# Transistor_Tester.net
KiCad netlist of a schematic drawn in EAGLE
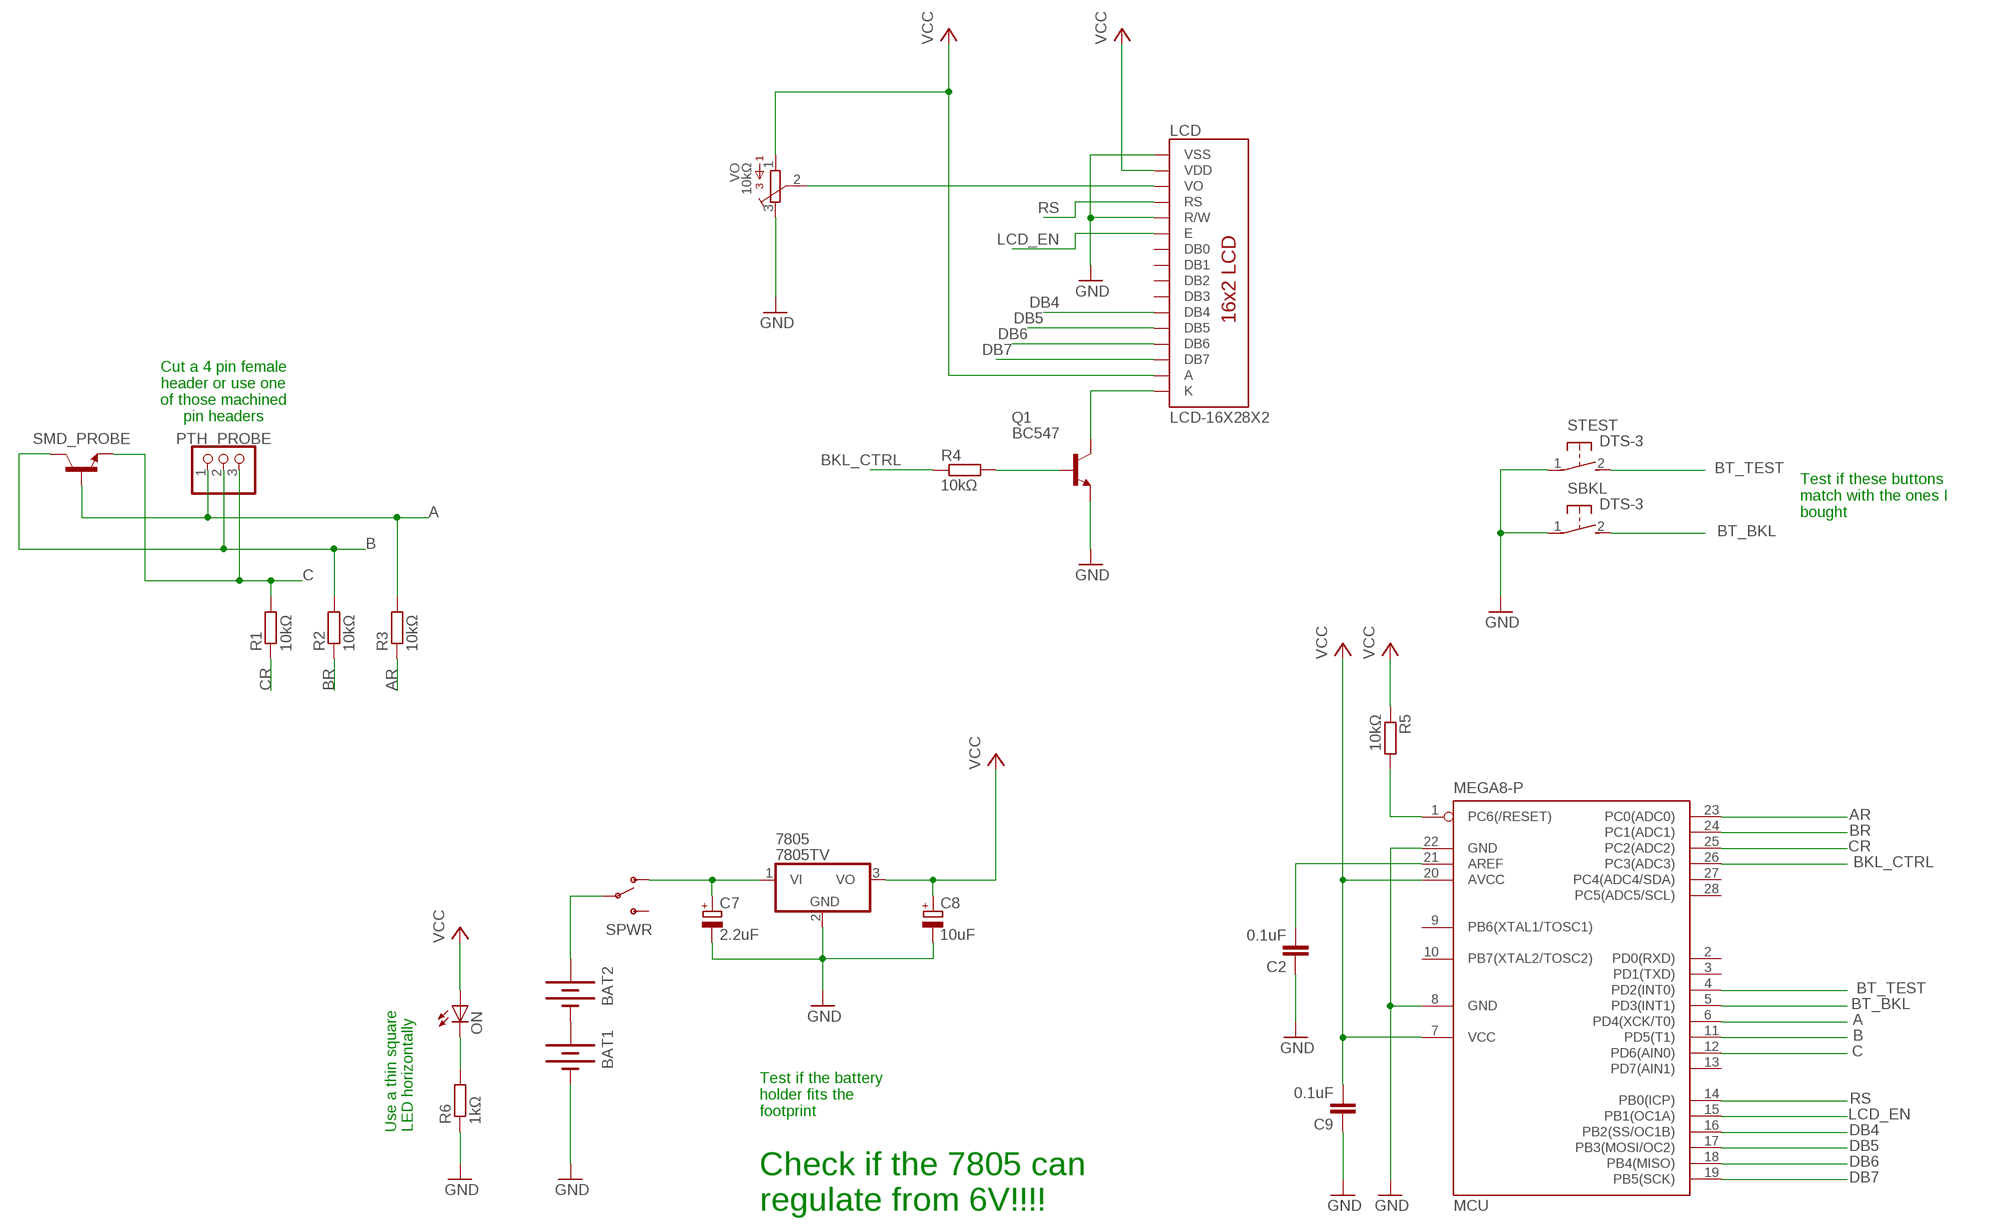
[diagram p0: schematic, sheet 1]

(export (version "E")
  (design (tool "Eeschema 10.0.6"))
  (components
    (comp (ref "7805")
      (value "7805TV")
      (footprint "eagle-import:TO220V")
      (libsource (lib "eagle-import") (part "78TV05"))
    )
    (comp (ref "BAT1")
      (value "20mm coincell")
      (footprint "eagle-import:BATTCON_20MM_4LEGS")
      (libsource (lib "eagle-import") (part "BATTERY20MM_4LEGS"))
    )
    (comp (ref "BAT2")
      (value "20mm coincell")
      (footprint "eagle-import:BATTCON_20MM_4LEGS")
      (libsource (lib "eagle-import") (part "BATTERY20MM_4LEGS"))
    )
    (comp (ref "C2")
      (value "0.1uF")
      (footprint "eagle-import:C025-025X050")
      (libsource (lib "eagle-import") (part "C-EU025-025X050"))
    )
    (comp (ref "C7")
      (value "2.2uF")
      (footprint "eagle-import:E2,5-6")
      (libsource (lib "eagle-import") (part "CPOL-EUE2.5-6"))
    )
    (comp (ref "C8")
      (value "10uF")
      (footprint "eagle-import:E2,5-6")
      (libsource (lib "eagle-import") (part "CPOL-EUE2.5-6"))
    )
    (comp (ref "C9")
      (value "0.1uF")
      (footprint "eagle-import:C050-025X075")
      (libsource (lib "eagle-import") (part "C-EU050-025X075"))
    )
    (comp (ref "LCD")
      (value "LCD-16X28X2")
      (footprint "eagle-import:LCD-8X2")
      (libsource (lib "eagle-import") (part "LCD-16X28X2"))
    )
    (comp (ref "MCU")
      (value "MEGA8-P")
      (footprint "eagle-import:DIL28-3")
      (libsource (lib "eagle-import") (part "MEGA8-P"))
    )
    (comp (ref "ON")
      (value "LED3MM")
      (footprint "eagle-import:LED3MM")
      (libsource (lib "eagle-import") (part "LED3MM"))
    )
    (comp (ref "PTH_PROBE")
      (value "PINHD-1X3")
      (footprint "eagle-import:1X03")
      (libsource (lib "eagle-import") (part "PINHD-1X3"))
    )
    (comp (ref "Q1")
      (value "BC547")
      (footprint "eagle-import:TO92")
      (libsource (lib "eagle-import") (part "BC547"))
    )
    (comp (ref "R1")
      (value "10kΩ")
      (footprint "eagle-import:0207_10")
      (libsource (lib "eagle-import") (part "resistor_R-EU_0207/10"))
    )
    (comp (ref "R2")
      (value "10kΩ")
      (footprint "eagle-import:0207_10")
      (libsource (lib "eagle-import") (part "resistor_R-EU_0207/10"))
    )
    (comp (ref "R3")
      (value "10kΩ")
      (footprint "eagle-import:0207_10")
      (libsource (lib "eagle-import") (part "resistor_R-EU_0207/10"))
    )
    (comp (ref "R4")
      (value "10kΩ")
      (footprint "eagle-import:0207_10")
      (libsource (lib "eagle-import") (part "R-EU_0207/10"))
    )
    (comp (ref "R5")
      (value "10kΩ")
      (footprint "eagle-import:0207_10")
      (libsource (lib "eagle-import") (part "R-EU_0207/10"))
    )
    (comp (ref "R6")
      (value "1kΩ")
      (footprint "eagle-import:0207_10")
      (libsource (lib "eagle-import") (part "R-EU_0207/10"))
    )
    (comp (ref "SBKL")
      (value "DTS-3")
      (footprint "eagle-import:DTS-3")
      (libsource (lib "eagle-import") (part "DTS-3"))
    )
    (comp (ref "SMD_PROBE")
      (value "BC817-25SMD")
      (footprint "eagle-import:SOT23-BEC")
      (libsource (lib "eagle-import") (part "BC817SMD-25"))
    )
    (comp (ref "SPWR")
      (value "SWITCH-SPDTPTH")
      (footprint "eagle-import:SWITCH-SPDT")
      (libsource (lib "eagle-import") (part "SWITCH-SPDTPTH"))
    )
    (comp (ref "STEST")
      (value "DTS-3")
      (footprint "eagle-import:DTS-3")
      (libsource (lib "eagle-import") (part "DTS-3"))
    )
    (comp (ref "VO")
      (value "10kΩ")
      (footprint "eagle-import:3362H")
      (libsource (lib "eagle-import") (part "3362H"))
    )
  )
  (nets
    (net (code "1") (name "/A") (class "Default")
      (node (ref "MCU") (pin "6") (pinfunction "PD4(XCK/T0)_6") (pintype "bidirectional"))
      (node (ref "PTH_PROBE") (pin "1") (pinfunction "1_1") (pintype "passive"))
      (node (ref "R3") (pin "2") (pinfunction "2_2") (pintype "passive"))
      (node (ref "SMD_PROBE") (pin "B") (pinfunction "B_B") (pintype "passive"))
    )
    (net (code "2") (name "/AR") (class "Default")
      (node (ref "MCU") (pin "23") (pinfunction "PC0(ADC0)_23") (pintype "bidirectional"))
      (node (ref "R3") (pin "1") (pinfunction "1_1") (pintype "passive"))
    )
    (net (code "3") (name "/B") (class "Default")
      (node (ref "MCU") (pin "11") (pinfunction "PD5(T1)_11") (pintype "bidirectional"))
      (node (ref "PTH_PROBE") (pin "2") (pinfunction "2_2") (pintype "passive"))
      (node (ref "R2") (pin "2") (pinfunction "2_2") (pintype "passive"))
      (node (ref "SMD_PROBE") (pin "C") (pinfunction "C_C") (pintype "passive"))
    )
    (net (code "4") (name "/BKL_CTRL") (class "Default")
      (node (ref "MCU") (pin "26") (pinfunction "PC3(ADC3)_26") (pintype "bidirectional"))
      (node (ref "R4") (pin "1") (pinfunction "1_1") (pintype "passive"))
    )
    (net (code "5") (name "/BR") (class "Default")
      (node (ref "MCU") (pin "24") (pinfunction "PC1(ADC1)_24") (pintype "bidirectional"))
      (node (ref "R2") (pin "1") (pinfunction "1_1") (pintype "passive"))
    )
    (net (code "6") (name "/BT_BKL") (class "Default")
      (node (ref "MCU") (pin "5") (pinfunction "PD3(INT1)_5") (pintype "bidirectional"))
      (node (ref "SBKL") (pin "2") (pinfunction "2_2") (pintype "passive"))
    )
    (net (code "7") (name "/BT_TEST") (class "Default")
      (node (ref "MCU") (pin "4") (pinfunction "PD2(INT0)_4") (pintype "bidirectional"))
      (node (ref "STEST") (pin "2") (pinfunction "2_2") (pintype "passive"))
    )
    (net (code "8") (name "/C") (class "Default")
      (node (ref "MCU") (pin "12") (pinfunction "PD6(AIN0)_12") (pintype "bidirectional"))
      (node (ref "PTH_PROBE") (pin "3") (pinfunction "3_3") (pintype "passive"))
      (node (ref "R1") (pin "2") (pinfunction "2_2") (pintype "passive"))
      (node (ref "SMD_PROBE") (pin "E") (pinfunction "E_E") (pintype "passive"))
    )
    (net (code "9") (name "/CR") (class "Default")
      (node (ref "MCU") (pin "25") (pinfunction "PC2(ADC2)_25") (pintype "bidirectional"))
      (node (ref "R1") (pin "1") (pinfunction "1_1") (pintype "passive"))
    )
    (net (code "10") (name "/DB4") (class "Default")
      (node (ref "LCD") (pin "11") (pinfunction "DB4_11") (pintype "bidirectional"))
      (node (ref "MCU") (pin "16") (pinfunction "PB2(SS/OC1B)_16") (pintype "bidirectional"))
    )
    (net (code "11") (name "/DB5") (class "Default")
      (node (ref "LCD") (pin "12") (pinfunction "DB5_12") (pintype "bidirectional"))
      (node (ref "MCU") (pin "17") (pinfunction "PB3(MOSI/OC2)_17") (pintype "bidirectional"))
    )
    (net (code "12") (name "/DB6") (class "Default")
      (node (ref "LCD") (pin "13") (pinfunction "DB6_13") (pintype "bidirectional"))
      (node (ref "MCU") (pin "18") (pinfunction "PB4(MISO)_18") (pintype "bidirectional"))
    )
    (net (code "13") (name "/DB7") (class "Default")
      (node (ref "LCD") (pin "14") (pinfunction "DB7_14") (pintype "bidirectional"))
      (node (ref "MCU") (pin "19") (pinfunction "PB5(SCK)_19") (pintype "bidirectional"))
    )
    (net (code "14") (name "/LCD_EN") (class "Default")
      (node (ref "LCD") (pin "6") (pinfunction "E_6") (pintype "input"))
      (node (ref "MCU") (pin "15") (pinfunction "PB1(OC1A)_15") (pintype "bidirectional"))
    )
    (net (code "15") (name "/RS") (class "Default")
      (node (ref "LCD") (pin "4") (pinfunction "RS_4") (pintype "input"))
      (node (ref "MCU") (pin "14") (pinfunction "PB0(ICP)_14") (pintype "bidirectional"))
    )
    (net (code "16") (name "GND") (class "Default")
      (node (ref "7805") (pin "2") (pinfunction "GND_2") (pintype "passive"))
      (node (ref "BAT1") (pin "2") (pinfunction "-_2") (pintype "power_in"))
      (node (ref "C2") (pin "1") (pinfunction "1_1") (pintype "passive"))
      (node (ref "C7") (pin "-") (pinfunction "-_-") (pintype "passive"))
      (node (ref "C8") (pin "-") (pinfunction "-_-") (pintype "passive"))
      (node (ref "C9") (pin "1") (pinfunction "1_1") (pintype "passive"))
      (node (ref "LCD") (pin "1") (pinfunction "VSS_1") (pintype "power_in"))
      (node (ref "LCD") (pin "5") (pinfunction "R/W_5") (pintype "input"))
      (node (ref "MCU") (pin "22") (pinfunction "GND_22") (pintype "power_in"))
      (node (ref "MCU") (pin "8") (pinfunction "GND_8") (pintype "power_in"))
      (node (ref "Q1") (pin "1") (pinfunction "E_1") (pintype "passive"))
      (node (ref "R6") (pin "1") (pinfunction "1_1") (pintype "passive"))
      (node (ref "SBKL") (pin "1") (pinfunction "1_1") (pintype "passive"))
      (node (ref "STEST") (pin "1") (pinfunction "1_1") (pintype "passive"))
      (node (ref "VO") (pin "3") (pinfunction "3_3") (pintype "passive"))
    )
    (net (code "17") (name "Net-(7805-VI)") (class "Default")
      (node (ref "7805") (pin "1") (pinfunction "VI_1") (pintype "input"))
      (node (ref "C7") (pin "+") (pinfunction "+_+") (pintype "passive"))
      (node (ref "SPWR") (pin "1") (pinfunction "O_1") (pintype "passive"))
    )
    (net (code "18") (name "Net-(BAT1-+)") (class "Default")
      (node (ref "BAT1") (pin "1") (pinfunction "+_1") (pintype "power_in"))
      (node (ref "BAT2") (pin "2") (pinfunction "-_2") (pintype "power_in"))
    )
    (net (code "19") (name "Net-(BAT2-+)") (class "Default")
      (node (ref "BAT2") (pin "1") (pinfunction "+_1") (pintype "power_in"))
      (node (ref "SPWR") (pin "2") (pinfunction "P_2") (pintype "passive"))
    )
    (net (code "20") (name "Net-(LCD-K)") (class "Default")
      (node (ref "LCD") (pin "16") (pinfunction "K_16") (pintype "power_in"))
      (node (ref "Q1") (pin "3") (pinfunction "C_3") (pintype "passive"))
    )
    (net (code "21") (name "Net-(LCD-VO)") (class "Default")
      (node (ref "LCD") (pin "3") (pinfunction "VO_3") (pintype "bidirectional"))
      (node (ref "VO") (pin "2") (pinfunction "2_2") (pintype "passive"))
    )
    (net (code "22") (name "Net-(MCU-AREF)") (class "Default")
      (node (ref "C2") (pin "2") (pinfunction "2_2") (pintype "passive"))
      (node (ref "MCU") (pin "21") (pinfunction "AREF_21") (pintype "passive"))
    )
    (net (code "23") (name "Net-(MCU-PC6({slash}RESET))") (class "Default")
      (node (ref "MCU") (pin "1") (pinfunction "PC6(/RESET)_1") (pintype "bidirectional"))
      (node (ref "R5") (pin "2") (pinfunction "2_2") (pintype "passive"))
    )
    (net (code "24") (name "Net-(ON-C)") (class "Default")
      (node (ref "ON") (pin "K") (pinfunction "C_K") (pintype "passive"))
      (node (ref "R6") (pin "2") (pinfunction "2_2") (pintype "passive"))
    )
    (net (code "25") (name "Net-(Q1-B)") (class "Default")
      (node (ref "Q1") (pin "2") (pinfunction "B_2") (pintype "passive"))
      (node (ref "R4") (pin "2") (pinfunction "2_2") (pintype "passive"))
    )
    (net (code "26") (name "VCC") (class "Default")
      (node (ref "7805") (pin "3") (pinfunction "VO_3") (pintype "passive"))
      (node (ref "C8") (pin "+") (pinfunction "+_+") (pintype "passive"))
      (node (ref "C9") (pin "2") (pinfunction "2_2") (pintype "passive"))
      (node (ref "LCD") (pin "15") (pinfunction "A_15") (pintype "power_in"))
      (node (ref "LCD") (pin "2") (pinfunction "VDD_2") (pintype "power_in"))
      (node (ref "MCU") (pin "20") (pinfunction "AVCC_20") (pintype "power_in"))
      (node (ref "MCU") (pin "7") (pinfunction "VCC_7") (pintype "power_in"))
      (node (ref "ON") (pin "A") (pinfunction "A_A") (pintype "passive"))
      (node (ref "R5") (pin "1") (pinfunction "1_1") (pintype "passive"))
      (node (ref "VO") (pin "1") (pinfunction "1_1") (pintype "passive"))
    )
    (net (code "27") (name "unconnected-(LCD-DB0-Pad7)") (class "Default")
      (node (ref "LCD") (pin "7") (pinfunction "DB0_7") (pintype "bidirectional"))
    )
    (net (code "28") (name "unconnected-(LCD-DB1-Pad8)") (class "Default")
      (node (ref "LCD") (pin "8") (pinfunction "DB1_8") (pintype "bidirectional"))
    )
    (net (code "29") (name "unconnected-(LCD-DB2-Pad9)") (class "Default")
      (node (ref "LCD") (pin "9") (pinfunction "DB2_9") (pintype "bidirectional"))
    )
    (net (code "30") (name "unconnected-(LCD-DB3-Pad10)") (class "Default")
      (node (ref "LCD") (pin "10") (pinfunction "DB3_10") (pintype "bidirectional"))
    )
    (net (code "31") (name "unconnected-(MCU-PB6(XTAL1{slash}TOSC1)-Pad9)") (class "Default")
      (node (ref "MCU") (pin "9") (pinfunction "PB6(XTAL1/TOSC1)_9") (pintype "bidirectional"))
    )
    (net (code "32") (name "unconnected-(MCU-PB7(XTAL2{slash}TOSC2)-Pad10)") (class "Default")
      (node (ref "MCU") (pin "10") (pinfunction "PB7(XTAL2/TOSC2)_10") (pintype "bidirectional"))
    )
    (net (code "33") (name "unconnected-(MCU-PC4(ADC4{slash}SDA)-Pad27)") (class "Default")
      (node (ref "MCU") (pin "27") (pinfunction "PC4(ADC4/SDA)_27") (pintype "bidirectional"))
    )
    (net (code "34") (name "unconnected-(MCU-PC5(ADC5{slash}SCL)-Pad28)") (class "Default")
      (node (ref "MCU") (pin "28") (pinfunction "PC5(ADC5/SCL)_28") (pintype "bidirectional"))
    )
    (net (code "35") (name "unconnected-(MCU-PD0(RXD)-Pad2)") (class "Default")
      (node (ref "MCU") (pin "2") (pinfunction "PD0(RXD)_2") (pintype "bidirectional"))
    )
    (net (code "36") (name "unconnected-(MCU-PD1(TXD)-Pad3)") (class "Default")
      (node (ref "MCU") (pin "3") (pinfunction "PD1(TXD)_3") (pintype "bidirectional"))
    )
    (net (code "37") (name "unconnected-(MCU-PD7(AIN1)-Pad13)") (class "Default")
      (node (ref "MCU") (pin "13") (pinfunction "PD7(AIN1)_13") (pintype "bidirectional"))
    )
    (net (code "38") (name "unconnected-(SPWR-S-Pad3)") (class "Default")
      (node (ref "SPWR") (pin "3") (pinfunction "S_3") (pintype "passive"))
    )
  )
)
